# EEL3111C_Lab_10_Schematic.net
KiCad netlist of a schematic drawn in Altium Designer
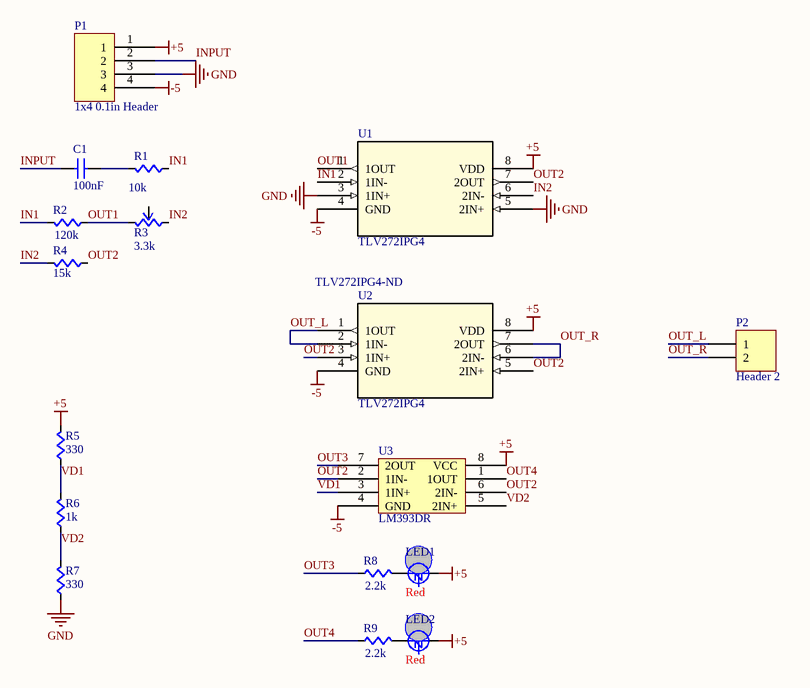
[diagram p0: EEL3111C Lab 10 Schematic.SchDoc]

(export (version "E")
  (design (tool "Eeschema 10.0.6"))
  (components
    (comp (ref "C1")
      (value "100nF")
      (footprint "CAPC0603")
      (fields (field (name "Comment") "Cap"))
      (libsource (lib "Passives") (part "Cap"))
    )
    (comp (ref "LED1")
      (value "LED")
      (footprint "LED0603")
      (fields (field (name "COLOR") "Red"))
      (libsource (lib "Semiconductors") (part "LED"))
    )
    (comp (ref "LED2")
      (value "LED")
      (footprint "LED0603")
      (fields (field (name "COLOR") "Red"))
      (libsource (lib "Semiconductors") (part "LED"))
    )
    (comp (ref "P1")
      (value "1x4 0.1in Header")
      (footprint "1x4 0.1in Header")
      (libsource (lib "Connectors") (part "1x4 0.1in Header"))
    )
    (comp (ref "P2")
      (value "Header 2")
      (footprint "HDR1X2")
      (description "Header, 2-Pin")
      (fields (field (name "PUBLISHER") "Altium Limited"))
      (libsource (lib "Miscellaneous Connectors") (part "Header 2"))
    )
    (comp (ref "R1")
      (value "10k")
      (footprint "RES0603")
      (fields (field (name "Comment") "Res"))
      (libsource (lib "Passives") (part "Res"))
    )
    (comp (ref "R2")
      (value "120k")
      (footprint "RES0603")
      (fields (field (name "Comment") "Res"))
      (libsource (lib "Passives") (part "Res"))
    )
    (comp (ref "R3")
      (value "3.3k")
      (footprint "ST4ETA103")
      (description "Potentiometer")
      (fields (field (name "Comment") "Pot"))
      (libsource (lib "Passives") (part "Potentiometer"))
    )
    (comp (ref "R4")
      (value "15k")
      (footprint "RES0603")
      (fields (field (name "Comment") "Res"))
      (libsource (lib "Passives") (part "Res"))
    )
    (comp (ref "R5")
      (value "330")
      (footprint "RES0603")
      (fields (field (name "Comment") "Res"))
      (libsource (lib "Passives") (part "Res"))
    )
    (comp (ref "R6")
      (value "1k")
      (footprint "RES0603")
      (fields (field (name "Comment") "Res"))
      (libsource (lib "Passives") (part "Res"))
    )
    (comp (ref "R7")
      (value "330")
      (footprint "RES0603")
      (fields (field (name "Comment") "Res"))
      (libsource (lib "Passives") (part "Res"))
    )
    (comp (ref "R8")
      (value "2.2k")
      (footprint "RES0603")
      (fields (field (name "Comment") "Res"))
      (libsource (lib "Passives") (part "Res"))
    )
    (comp (ref "R9")
      (value "2.2k")
      (footprint "RES0603")
      (fields (field (name "Comment") "Res"))
      (libsource (lib "Passives") (part "Res"))
    )
    (comp (ref "U1")
      (value "TLV272IPG4")
      (footprint "P8_TEX")
      (description "No Description Available")
      (fields (field (name "COPYRIGHT") "Copyright (C) 2021 Ultra Librarian. All rights reserved."))
      (libsource (lib "Schlib1") (part "TLV272IPG4"))
    )
    (comp (ref "U2")
      (value "TLV272IPG4")
      (footprint "P8_TEX")
      (description "No Description Available")
      (fields
        (field (name "SUPPLIER PART NUMBER 1") "TLV272IPG4-ND")
        (field (name "COPYRIGHT") "Copyright (C) 2021 Ultra Librarian. All rights reserved.")
      )
      (libsource (lib "Schlib1") (part "TLV272IPG4"))
    )
    (comp (ref "U3")
      (value "LM393DR")
      (footprint "LM393DR")
      (description "LM393DR Comparator")
      (libsource (lib "ICs") (part "LM393DR"))
    )
  )
  (nets
    (net (code "1") (name "+5") (class "Default")
      (node (ref "LED1") (pin "A") (pinfunction "A_A") (pintype "passive"))
      (node (ref "LED2") (pin "A") (pinfunction "A_A") (pintype "passive"))
      (node (ref "P1") (pin "1") (pinfunction "1_1") (pintype "passive"))
      (node (ref "R5") (pin "1") (pinfunction "A_1") (pintype "passive"))
      (node (ref "U1") (pin "8") (pinfunction "VDD_8") (pintype "power_in"))
      (node (ref "U2") (pin "8") (pinfunction "VDD_8") (pintype "power_in"))
      (node (ref "U3") (pin "8") (pinfunction "VCC_8") (pintype "passive"))
    )
    (net (code "2") (name "-5") (class "Default")
      (node (ref "P1") (pin "4") (pinfunction "4_4") (pintype "passive"))
      (node (ref "U1") (pin "4") (pinfunction "GND_4") (pintype "power_in"))
      (node (ref "U2") (pin "4") (pinfunction "GND_4") (pintype "power_in"))
      (node (ref "U3") (pin "4") (pinfunction "GND_4") (pintype "passive"))
    )
    (net (code "3") (name "/IN1") (class "Default")
      (node (ref "R1") (pin "2") (pinfunction "B_2") (pintype "passive"))
      (node (ref "R2") (pin "1") (pinfunction "A_1") (pintype "passive"))
      (node (ref "U1") (pin "2") (pinfunction "1IN-_2") (pintype "input"))
    )
    (net (code "4") (name "/IN2") (class "Default")
      (node (ref "R3") (pin "2") (pinfunction "2_2") (pintype "passive"))
      (node (ref "R4") (pin "1") (pinfunction "A_1") (pintype "passive"))
      (node (ref "U1") (pin "6") (pinfunction "2IN-_6") (pintype "input"))
    )
    (net (code "5") (name "/INPUT") (class "Default")
      (node (ref "C1") (pin "1") (pinfunction "A_1") (pintype "passive"))
      (node (ref "P1") (pin "2") (pinfunction "2_2") (pintype "passive"))
    )
    (net (code "6") (name "/OUT1") (class "Default")
      (node (ref "R2") (pin "2") (pinfunction "B_2") (pintype "passive"))
      (node (ref "R3") (pin "1") (pinfunction "1_1") (pintype "passive"))
      (node (ref "U1") (pin "1") (pinfunction "1OUT_1") (pintype "output"))
    )
    (net (code "7") (name "/OUT2") (class "Default")
      (node (ref "R4") (pin "2") (pinfunction "B_2") (pintype "passive"))
      (node (ref "U1") (pin "7") (pinfunction "2OUT_7") (pintype "output"))
      (node (ref "U2") (pin "3") (pinfunction "1IN+_3") (pintype "input"))
      (node (ref "U2") (pin "5") (pinfunction "2IN+_5") (pintype "input"))
      (node (ref "U3") (pin "2") (pinfunction "1IN-_2") (pintype "passive"))
      (node (ref "U3") (pin "6") (pinfunction "2IN-_6") (pintype "passive"))
    )
    (net (code "8") (name "/OUT3") (class "Default")
      (node (ref "R8") (pin "2") (pinfunction "B_2") (pintype "passive"))
      (node (ref "U3") (pin "7") (pinfunction "2OUT_7") (pintype "passive"))
    )
    (net (code "9") (name "/OUT4") (class "Default")
      (node (ref "R9") (pin "2") (pinfunction "B_2") (pintype "passive"))
      (node (ref "U3") (pin "1") (pinfunction "1OUT_1") (pintype "passive"))
    )
    (net (code "10") (name "/OUT_L") (class "Default")
      (node (ref "P2") (pin "1") (pinfunction "1_1") (pintype "passive"))
      (node (ref "U2") (pin "1") (pinfunction "1OUT_1") (pintype "output"))
      (node (ref "U2") (pin "2") (pinfunction "1IN-_2") (pintype "input"))
    )
    (net (code "11") (name "/OUT_R") (class "Default")
      (node (ref "P2") (pin "2") (pinfunction "2_2") (pintype "passive"))
      (node (ref "U2") (pin "6") (pinfunction "2IN-_6") (pintype "input"))
      (node (ref "U2") (pin "7") (pinfunction "2OUT_7") (pintype "output"))
    )
    (net (code "12") (name "/VD1") (class "Default")
      (node (ref "R5") (pin "2") (pinfunction "B_2") (pintype "passive"))
      (node (ref "R6") (pin "1") (pinfunction "A_1") (pintype "passive"))
      (node (ref "U3") (pin "3") (pinfunction "1IN+_3") (pintype "passive"))
    )
    (net (code "13") (name "/VD2") (class "Default")
      (node (ref "R6") (pin "2") (pinfunction "B_2") (pintype "passive"))
      (node (ref "R7") (pin "1") (pinfunction "A_1") (pintype "passive"))
      (node (ref "U3") (pin "5") (pinfunction "2IN+_5") (pintype "passive"))
    )
    (net (code "14") (name "GND") (class "Default")
      (node (ref "P1") (pin "3") (pinfunction "3_3") (pintype "passive"))
      (node (ref "R7") (pin "2") (pinfunction "B_2") (pintype "passive"))
      (node (ref "U1") (pin "3") (pinfunction "1IN+_3") (pintype "input"))
      (node (ref "U1") (pin "5") (pinfunction "2IN+_5") (pintype "input"))
    )
    (net (code "15") (name "Net-(C1-B)") (class "Default")
      (node (ref "C1") (pin "2") (pinfunction "B_2") (pintype "passive"))
      (node (ref "R1") (pin "1") (pinfunction "A_1") (pintype "passive"))
    )
    (net (code "16") (name "Net-(R8-A)") (class "Default")
      (node (ref "LED1") (pin "C") (pinfunction "C_C") (pintype "passive"))
      (node (ref "R8") (pin "1") (pinfunction "A_1") (pintype "passive"))
    )
    (net (code "17") (name "Net-(R9-A)") (class "Default")
      (node (ref "LED2") (pin "C") (pinfunction "C_C") (pintype "passive"))
      (node (ref "R9") (pin "1") (pinfunction "A_1") (pintype "passive"))
    )
    (net (code "18") (name "unconnected-(R3-Pad3)") (class "Default")
      (node (ref "R3") (pin "3") (pinfunction "3_3") (pintype "passive"))
    )
  )
)
